# MEOWPOWER.net
KiCad netlist of a schematic drawn in Altium Designer
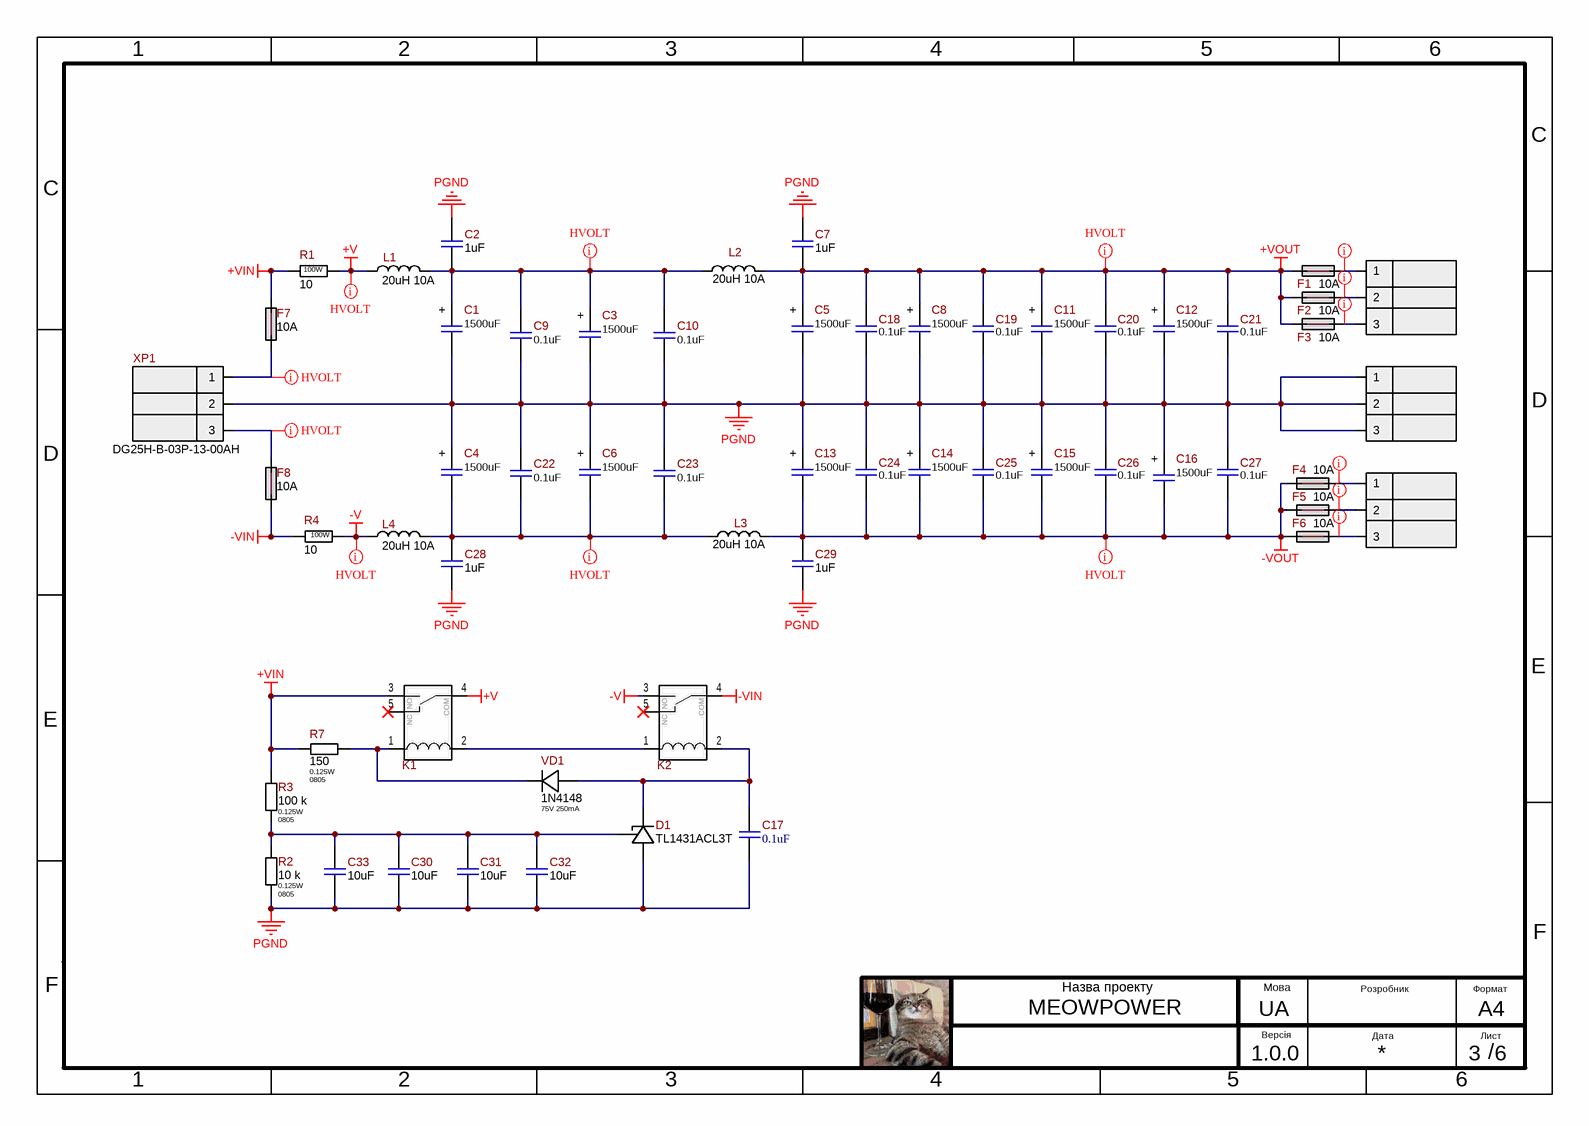
[diagram p0: MEOWPOWER.SchDoc]

(export (version "E")
  (design (tool "Eeschema 10.0.6"))
  (components
    (comp (ref "C1")
      (value "1500uF")
      (footprint "CAP-AE-PTH-180D05x400H20")
      (description "1500uF 50V")
      (fields (field (name "PART NUMBER") "1500uF  50V 18x35") (field (name "TOLERANCE") "±10%"))
      (libsource (lib "Database") (part "Capacitor_Electrolytic"))
    )
    (comp (ref "C2")
      (value "1uF")
      (footprint "CAP 25x10MM")
      (description "MKP 1uF 275V")
      (fields (field (name "PART NUMBER") "1uF  275V 25x10") (field (name "TOLERANCE") "±10%"))
      (libsource (lib "Database") (part "Capacitor_Ceramic"))
    )
    (comp (ref "C3")
      (value "1500uF")
      (footprint "CAP-AE-PTH-180D05x400H20")
      (description "1500uF 50V")
      (fields (field (name "PART NUMBER") "1500uF  50V 18x35") (field (name "TOLERANCE") "±10%"))
      (libsource (lib "Database") (part "Capacitor_Electrolytic"))
    )
    (comp (ref "C4")
      (value "1500uF")
      (footprint "CAP-AE-PTH-180D05x400H20")
      (description "1500uF 50V")
      (fields (field (name "PART NUMBER") "1500uF  50V 18x35") (field (name "TOLERANCE") "±10%"))
      (libsource (lib "Database") (part "Capacitor_Electrolytic"))
    )
    (comp (ref "C5")
      (value "1500uF")
      (footprint "CAP-AE-PTH-180D05x400H20")
      (description "1500uF 50V")
      (fields (field (name "PART NUMBER") "1500uF  50V 18x35") (field (name "TOLERANCE") "±10%"))
      (libsource (lib "Database") (part "Capacitor_Electrolytic"))
    )
    (comp (ref "C6")
      (value "1500uF")
      (footprint "CAP-AE-PTH-180D05x400H20")
      (description "1500uF 50V")
      (fields (field (name "PART NUMBER") "1500uF  50V 18x35") (field (name "TOLERANCE") "±10%"))
      (libsource (lib "Database") (part "Capacitor_Electrolytic"))
    )
    (comp (ref "C7")
      (value "1uF")
      (footprint "CAP 25x10MM")
      (description "MKP 1uF 275V")
      (fields (field (name "PART NUMBER") "1uF  275V 25x10") (field (name "TOLERANCE") "±10%"))
      (libsource (lib "Database") (part "Capacitor_Ceramic"))
    )
    (comp (ref "C8")
      (value "1500uF")
      (footprint "CAP-AE-PTH-180D05x400H20")
      (description "1500uF 50V")
      (fields (field (name "PART NUMBER") "1500uF  50V 18x35") (field (name "TOLERANCE") "±10%"))
      (libsource (lib "Database") (part "Capacitor_Electrolytic"))
    )
    (comp (ref "C9")
      (value "0.1uF")
      (footprint "C1206(3216)")
      (description "CAP CER 0.1UF 50V X7R 1206")
      (fields (field (name "PART NUMBER") "0.1uF  50V С1206") (field (name "MANUFACTURER") "AVX Corporation"))
      (libsource (lib "Database") (part "Capacitor_Ceramic"))
    )
    (comp (ref "C10")
      (value "0.1uF")
      (footprint "C1206(3216)")
      (description "CAP CER 0.1UF 50V X7R 1206")
      (fields (field (name "PART NUMBER") "0.1uF  50V С1206") (field (name "MANUFACTURER") "AVX Corporation"))
      (libsource (lib "Database") (part "Capacitor_Ceramic"))
    )
    (comp (ref "C11")
      (value "1500uF")
      (footprint "CAP-AE-PTH-180D05x400H20")
      (description "1500uF 50V")
      (fields (field (name "PART NUMBER") "1500uF  50V 18x35") (field (name "TOLERANCE") "±10%"))
      (libsource (lib "Database") (part "Capacitor_Electrolytic"))
    )
    (comp (ref "C12")
      (value "1500uF")
      (footprint "CAP-AE-PTH-180D05x400H20")
      (description "1500uF 50V")
      (fields (field (name "PART NUMBER") "1500uF  50V 18x35") (field (name "TOLERANCE") "±10%"))
      (libsource (lib "Database") (part "Capacitor_Electrolytic"))
    )
    (comp (ref "C13")
      (value "1500uF")
      (footprint "CAP-AE-PTH-180D05x400H20")
      (description "1500uF 50V")
      (fields (field (name "PART NUMBER") "1500uF  50V 18x35") (field (name "TOLERANCE") "±10%"))
      (libsource (lib "Database") (part "Capacitor_Electrolytic"))
    )
    (comp (ref "C14")
      (value "1500uF")
      (footprint "CAP-AE-PTH-180D05x400H20")
      (description "1500uF 50V")
      (fields (field (name "PART NUMBER") "1500uF  50V 18x35") (field (name "TOLERANCE") "±10%"))
      (libsource (lib "Database") (part "Capacitor_Electrolytic"))
    )
    (comp (ref "C15")
      (value "1500uF")
      (footprint "CAP-AE-PTH-180D05x400H20")
      (description "1500uF 50V")
      (fields (field (name "PART NUMBER") "1500uF  50V 18x35") (field (name "TOLERANCE") "±10%"))
      (libsource (lib "Database") (part "Capacitor_Electrolytic"))
    )
    (comp (ref "C16")
      (value "1500uF")
      (footprint "CAP-AE-PTH-180D05x400H20")
      (description "1500uF 50V")
      (fields (field (name "PART NUMBER") "1500uF  50V 18x35") (field (name "TOLERANCE") "±10%"))
      (libsource (lib "Database") (part "Capacitor_Electrolytic"))
    )
    (comp (ref "C17")
      (value "0.1uF")
      (footprint "C0805(2012)")
      (description "CAP CER 0.1UF 50V X7R 0805")
      (fields (field (name "PART NUMBER") "0.1uF  50V C0805") (field (name "MANUFACTURER") "AVX Corporation"))
      (libsource (lib "Database") (part "Capacitor_Ceramic"))
    )
    (comp (ref "C18")
      (value "0.1uF")
      (footprint "C1206(3216)")
      (description "CAP CER 0.1UF 50V X7R 1206")
      (fields (field (name "PART NUMBER") "0.1uF  50V С1206") (field (name "MANUFACTURER") "AVX Corporation"))
      (libsource (lib "Database") (part "Capacitor_Ceramic"))
    )
    (comp (ref "C19")
      (value "0.1uF")
      (footprint "C1206(3216)")
      (description "CAP CER 0.1UF 50V X7R 1206")
      (fields (field (name "PART NUMBER") "0.1uF  50V С1206") (field (name "MANUFACTURER") "AVX Corporation"))
      (libsource (lib "Database") (part "Capacitor_Ceramic"))
    )
    (comp (ref "C20")
      (value "0.1uF")
      (footprint "C1206(3216)")
      (description "CAP CER 0.1UF 50V X7R 1206")
      (fields (field (name "PART NUMBER") "0.1uF  50V С1206") (field (name "MANUFACTURER") "AVX Corporation"))
      (libsource (lib "Database") (part "Capacitor_Ceramic"))
    )
    (comp (ref "C21")
      (value "0.1uF")
      (footprint "C1206(3216)")
      (description "CAP CER 0.1UF 50V X7R 1206")
      (fields (field (name "PART NUMBER") "0.1uF  50V С1206") (field (name "MANUFACTURER") "AVX Corporation"))
      (libsource (lib "Database") (part "Capacitor_Ceramic"))
    )
    (comp (ref "C22")
      (value "0.1uF")
      (footprint "C1206(3216)")
      (description "CAP CER 0.1UF 50V X7R 1206")
      (fields (field (name "PART NUMBER") "0.1uF  50V С1206") (field (name "MANUFACTURER") "AVX Corporation"))
      (libsource (lib "Database") (part "Capacitor_Ceramic"))
    )
    (comp (ref "C23")
      (value "0.1uF")
      (footprint "C1206(3216)")
      (description "CAP CER 0.1UF 50V X7R 1206")
      (fields (field (name "PART NUMBER") "0.1uF  50V С1206") (field (name "MANUFACTURER") "AVX Corporation"))
      (libsource (lib "Database") (part "Capacitor_Ceramic"))
    )
    (comp (ref "C24")
      (value "0.1uF")
      (footprint "C1206(3216)")
      (description "CAP CER 0.1UF 50V X7R 1206")
      (fields (field (name "PART NUMBER") "0.1uF  50V С1206") (field (name "MANUFACTURER") "AVX Corporation"))
      (libsource (lib "Database") (part "Capacitor_Ceramic"))
    )
    (comp (ref "C25")
      (value "0.1uF")
      (footprint "C1206(3216)")
      (description "CAP CER 0.1UF 50V X7R 1206")
      (fields (field (name "PART NUMBER") "0.1uF  50V С1206") (field (name "MANUFACTURER") "AVX Corporation"))
      (libsource (lib "Database") (part "Capacitor_Ceramic"))
    )
    (comp (ref "C26")
      (value "0.1uF")
      (footprint "C1206(3216)")
      (description "CAP CER 0.1UF 50V X7R 1206")
      (fields (field (name "PART NUMBER") "0.1uF  50V С1206") (field (name "MANUFACTURER") "AVX Corporation"))
      (libsource (lib "Database") (part "Capacitor_Ceramic"))
    )
    (comp (ref "C27")
      (value "0.1uF")
      (footprint "C1206(3216)")
      (description "CAP CER 0.1UF 50V X7R 1206")
      (fields (field (name "PART NUMBER") "0.1uF  50V С1206") (field (name "MANUFACTURER") "AVX Corporation"))
      (libsource (lib "Database") (part "Capacitor_Ceramic"))
    )
    (comp (ref "C28")
      (value "1uF")
      (footprint "CAP 25x10MM")
      (description "MKP 1uF 275V")
      (fields (field (name "PART NUMBER") "1uF  275V 25x10") (field (name "TOLERANCE") "±10%"))
      (libsource (lib "Database") (part "Capacitor_Ceramic"))
    )
    (comp (ref "C29")
      (value "1uF")
      (footprint "CAP 25x10MM")
      (description "MKP 1uF 275V")
      (fields (field (name "PART NUMBER") "1uF  275V 25x10") (field (name "TOLERANCE") "±10%"))
      (libsource (lib "Database") (part "Capacitor_Ceramic"))
    )
    (comp (ref "C30")
      (value "10uF")
      (footprint "C0805(2012)")
      (description "CAP CER 10UF 16V X6S 0805")
      (fields (field (name "PART NUMBER") "10uF  16V C0805") (field (name "TOLERANCE") "±10%"))
      (libsource (lib "Database") (part "Capacitor_Ceramic"))
    )
    (comp (ref "C31")
      (value "10uF")
      (footprint "C0805(2012)")
      (description "CAP CER 10UF 16V X6S 0805")
      (fields (field (name "PART NUMBER") "10uF  16V C0805") (field (name "TOLERANCE") "±10%"))
      (libsource (lib "Database") (part "Capacitor_Ceramic"))
    )
    (comp (ref "C32")
      (value "10uF")
      (footprint "C0805(2012)")
      (description "CAP CER 10UF 16V X6S 0805")
      (fields (field (name "PART NUMBER") "10uF  16V C0805") (field (name "TOLERANCE") "±10%"))
      (libsource (lib "Database") (part "Capacitor_Ceramic"))
    )
    (comp (ref "C33")
      (value "10uF")
      (footprint "C0805(2012)")
      (description "CAP CER 10UF 16V X6S 0805")
      (fields (field (name "PART NUMBER") "10uF  16V C0805") (field (name "TOLERANCE") "±10%"))
      (libsource (lib "Database") (part "Capacitor_Ceramic"))
    )
    (comp (ref "D1")
      (value "TL1431ACL3T")
      (footprint "SOT-23")
      (description "IC VREF SHUNT ADJ  ±0.25% SOT23-3")
      (fields (field (name "PART NUMBER") "TL1431ACL3T") (field (name "MANUFACTURER") "STMicroelectronics"))
      (libsource (lib "Database") (part "TL431"))
    )
    (comp (ref "F1")
      (value "10A")
      (footprint "FUSE1808")
      (libsource (lib "Database") (part "Resettable_Fuses"))
    )
    (comp (ref "F2")
      (value "10A")
      (footprint "FUSE1808")
      (libsource (lib "Database") (part "Resettable_Fuses"))
    )
    (comp (ref "F3")
      (value "10A")
      (footprint "FUSE1808")
      (libsource (lib "Database") (part "Resettable_Fuses"))
    )
    (comp (ref "F4")
      (value "10A")
      (footprint "FUSE1808")
      (libsource (lib "Database") (part "Resettable_Fuses"))
    )
    (comp (ref "F5")
      (value "10A")
      (footprint "FUSE1808")
      (libsource (lib "Database") (part "Resettable_Fuses"))
    )
    (comp (ref "F6")
      (value "10A")
      (footprint "FUSE1808")
      (libsource (lib "Database") (part "Resettable_Fuses"))
    )
    (comp (ref "F7") (value "10A") (footprint "FUSE1808") (libsource (lib "") (part "Resettable_Fuses_1")))
    (comp (ref "F8") (value "10A") (footprint "FUSE1808") (libsource (lib "") (part "Resettable_Fuses_1")))
    (comp (ref "K1")
      (value "LEG-12")
      (footprint "Relay10A")
      (description "General Purpose Relay, 1 Form C (1PDT), 12VDC 400Ohm Coil, 120VAC/24VDC @ 10A, 240VAC Max")
      (libsource (lib "Database") (part "RELAY10A"))
    )
    (comp (ref "K2")
      (value "LEG-12")
      (footprint "Relay10A")
      (description "General Purpose Relay, 1 Form C (1PDT), 12VDC 400Ohm Coil, 120VAC/24VDC @ 10A, 240VAC Max")
      (libsource (lib "Database") (part "RELAY10A"))
    )
    (comp (ref "L1")
      (value "20uH 10A")
      (footprint "IND10x25x8.4")
      (description "CASTOM")
      (fields (field (name "TOLERANCE") "±10"))
      (libsource (lib "Database") (part "INDUCTORS"))
    )
    (comp (ref "L2")
      (value "20uH 10A")
      (footprint "IND10x25x8.4")
      (description "CASTOM")
      (fields (field (name "TOLERANCE") "±10"))
      (libsource (lib "Database") (part "INDUCTORS"))
    )
    (comp (ref "L3")
      (value "20uH 10A")
      (footprint "IND10x25x8.4")
      (description "CASTOM")
      (fields (field (name "TOLERANCE") "±10"))
      (libsource (lib "Database") (part "INDUCTORS"))
    )
    (comp (ref "L4")
      (value "20uH 10A")
      (footprint "IND10x25x8.4")
      (description "CASTOM")
      (fields (field (name "TOLERANCE") "±10"))
      (libsource (lib "Database") (part "INDUCTORS"))
    )
    (comp (ref "R1")
      (value "10")
      (footprint "RES_TO-247")
      (description "Resistror 10 OHM  ±5% TO-247 100W")
      (fields
        (field (name "POWER RATING") "100W")
        (field (name "PART NUMBER") "10  RES_TO-247")
        (field (name "TOLERANCE") "±5%")
      )
      (libsource (lib "Database") (part "RES_1W"))
    )
    (comp (ref "R2")
      (value "10 k")
      (footprint "R0805")
      (description "RES SMD 10 k OHM  ±1% 1/8W 0805")
      (fields
        (field (name "POWER RATING") "0.125W")
        (field (name "PACKAGE/CASE") "0805")
        (field (name "PART NUMBER") "10 k  R0805")
        (field (name "TOLERANCE") "±1%")
      )
      (libsource (lib "Database") (part "R0805"))
    )
    (comp (ref "R3")
      (value "100 k")
      (footprint "R0805")
      (description "RES SMD 100 k OHM  ±1% 1/8W 0805")
      (fields
        (field (name "POWER RATING") "0.125W")
        (field (name "PACKAGE/CASE") "0805")
        (field (name "PART NUMBER") "100 k  R0805")
        (field (name "TOLERANCE") "±1%")
      )
      (libsource (lib "Database") (part "R0805"))
    )
    (comp (ref "R4")
      (value "10")
      (footprint "RES_TO-247")
      (description "Resistror 10 OHM  ±5% TO-247 100W")
      (fields
        (field (name "POWER RATING") "100W")
        (field (name "PART NUMBER") "10  RES_TO-247")
        (field (name "TOLERANCE") "±5%")
      )
      (libsource (lib "Database") (part "RES_1W"))
    )
    (comp (ref "R7")
      (value "150")
      (footprint "R0805")
      (description "RES SMD 150 OHM  ±1% 1/8W 0805")
      (fields
        (field (name "POWER RATING") "0.125W")
        (field (name "PACKAGE/CASE") "0805")
        (field (name "PART NUMBER") "150  R0805")
        (field (name "TOLERANCE") "±1%")
      )
      (libsource (lib "Database") (part "R0805"))
    )
    (comp (ref "VD1")
      (value "1N4148")
      (footprint "SOD-80")
      (description "DIODE GEN PURP 75V 250MA SOD323")
      (fields (field (name "POWER RATING") "75V 250mA") (field (name "MANUFACTURER") "Diodes Incorporated"))
      (libsource (lib "Database") (part "DIODE"))
    )
    (comp (ref "XP1")
      (value "DG25H-B-03P-13-00AH")
      (footprint "DG25H-B-03P")
      (description "3PIN 7.62mm 300V 15 A  7-30 AWG")
      (libsource (lib "") (part "CON_3_1"))
    )
    (comp (ref "XP2")
      (value "DG25H-B-03P-13-00AH")
      (footprint "DG25H-B-03P")
      (description "3PIN 7.62mm 300V 15 A  7-30 AWG")
      (libsource (lib "Database") (part "CON_3"))
    )
    (comp (ref "XP3")
      (value "DG25H-B-03P-13-00AH")
      (footprint "DG25H-B-03P")
      (description "3PIN 7.62mm 300V 15 A  7-30 AWG")
      (libsource (lib "Database") (part "CON_3"))
    )
    (comp (ref "XP4")
      (value "DG25H-B-03P-13-00AH")
      (footprint "DG25H-B-03P")
      (description "3PIN 7.62mm 300V 15 A  7-30 AWG")
      (libsource (lib "Database") (part "CON_3"))
    )
  )
  (nets
    (net (code "1") (name "+V") (class "Default")
      (node (ref "K1") (pin "4") (pinfunction "COM_4") (pintype "passive"))
      (node (ref "L1") (pin "1") (pintype "passive"))
      (node (ref "R1") (pin "2") (pinfunction "2_2") (pintype "passive"))
    )
    (net (code "2") (name "+VIN") (class "Default")
      (node (ref "F7") (pin "2") (pinfunction "2_2") (pintype "passive"))
      (node (ref "K1") (pin "3") (pinfunction "NO_3") (pintype "passive"))
      (node (ref "R1") (pin "1") (pinfunction "1_1") (pintype "passive"))
      (node (ref "R3") (pin "2") (pinfunction "2_2") (pintype "passive"))
      (node (ref "R7") (pin "2") (pinfunction "2_2") (pintype "passive"))
    )
    (net (code "3") (name "+VOUT") (class "Default")
      (node (ref "C11") (pin "1") (pinfunction "1_1") (pintype "passive"))
      (node (ref "C12") (pin "1") (pinfunction "1_1") (pintype "passive"))
      (node (ref "C18") (pin "1") (pinfunction "1_1") (pintype "passive"))
      (node (ref "C19") (pin "1") (pinfunction "1_1") (pintype "passive"))
      (node (ref "C20") (pin "1") (pinfunction "1_1") (pintype "passive"))
      (node (ref "C21") (pin "1") (pinfunction "1_1") (pintype "passive"))
      (node (ref "C5") (pin "1") (pinfunction "1_1") (pintype "passive"))
      (node (ref "C7") (pin "2") (pinfunction "2_2") (pintype "passive"))
      (node (ref "C8") (pin "1") (pinfunction "1_1") (pintype "passive"))
      (node (ref "F1") (pin "1") (pinfunction "1_1") (pintype "passive"))
      (node (ref "F2") (pin "1") (pinfunction "1_1") (pintype "passive"))
      (node (ref "F3") (pin "1") (pinfunction "1_1") (pintype "passive"))
      (node (ref "L2") (pin "2") (pintype "passive"))
    )
    (net (code "4") (name "-V") (class "Default")
      (node (ref "K2") (pin "3") (pinfunction "NO_3") (pintype "passive"))
      (node (ref "L4") (pin "1") (pintype "passive"))
      (node (ref "R4") (pin "1") (pinfunction "1_1") (pintype "passive"))
    )
    (net (code "5") (name "-VIN") (class "Default")
      (node (ref "F8") (pin "1") (pinfunction "1_1") (pintype "passive"))
      (node (ref "K2") (pin "4") (pinfunction "COM_4") (pintype "passive"))
      (node (ref "R4") (pin "2") (pinfunction "2_2") (pintype "passive"))
    )
    (net (code "6") (name "-VOUT") (class "Default")
      (node (ref "C13") (pin "2") (pinfunction "2_2") (pintype "passive"))
      (node (ref "C14") (pin "2") (pinfunction "2_2") (pintype "passive"))
      (node (ref "C15") (pin "2") (pinfunction "2_2") (pintype "passive"))
      (node (ref "C16") (pin "2") (pinfunction "2_2") (pintype "passive"))
      (node (ref "C24") (pin "2") (pinfunction "2_2") (pintype "passive"))
      (node (ref "C25") (pin "2") (pinfunction "2_2") (pintype "passive"))
      (node (ref "C26") (pin "2") (pinfunction "2_2") (pintype "passive"))
      (node (ref "C27") (pin "2") (pinfunction "2_2") (pintype "passive"))
      (node (ref "C29") (pin "2") (pinfunction "2_2") (pintype "passive"))
      (node (ref "F4") (pin "1") (pinfunction "1_1") (pintype "passive"))
      (node (ref "F5") (pin "1") (pinfunction "1_1") (pintype "passive"))
      (node (ref "F6") (pin "1") (pinfunction "1_1") (pintype "passive"))
      (node (ref "L3") (pin "2") (pintype "passive"))
    )
    (net (code "7") (name "Net-(C1-Pad1)") (class "Default")
      (node (ref "C1") (pin "1") (pinfunction "1_1") (pintype "passive"))
      (node (ref "C10") (pin "2") (pinfunction "2_2") (pintype "passive"))
      (node (ref "C2") (pin "2") (pinfunction "2_2") (pintype "passive"))
      (node (ref "C3") (pin "1") (pinfunction "1_1") (pintype "passive"))
      (node (ref "C9") (pin "2") (pinfunction "2_2") (pintype "passive"))
      (node (ref "L1") (pin "2") (pintype "passive"))
      (node (ref "L2") (pin "1") (pintype "passive"))
    )
    (net (code "8") (name "Net-(C22-Pad1)") (class "Default")
      (node (ref "C22") (pin "1") (pinfunction "1_1") (pintype "passive"))
      (node (ref "C23") (pin "1") (pinfunction "1_1") (pintype "passive"))
      (node (ref "C28") (pin "2") (pinfunction "2_2") (pintype "passive"))
      (node (ref "C4") (pin "2") (pinfunction "2_2") (pintype "passive"))
      (node (ref "C6") (pin "2") (pinfunction "2_2") (pintype "passive"))
      (node (ref "L3") (pin "1") (pintype "passive"))
      (node (ref "L4") (pin "2") (pintype "passive"))
    )
    (net (code "9") (name "Net-(D1-C)") (class "Default")
      (node (ref "C17") (pin "2") (pinfunction "2_2") (pintype "passive"))
      (node (ref "D1") (pin "1") (pinfunction "C_1") (pintype "passive"))
      (node (ref "K2") (pin "2") (pintype "passive"))
      (node (ref "VD1") (pin "2") (pinfunction "A_2") (pintype "passive"))
    )
    (net (code "10") (name "Net-(D1-REF)") (class "Default")
      (node (ref "C30") (pin "2") (pinfunction "2_2") (pintype "passive"))
      (node (ref "C31") (pin "2") (pinfunction "2_2") (pintype "passive"))
      (node (ref "C32") (pin "2") (pinfunction "2_2") (pintype "passive"))
      (node (ref "C33") (pin "2") (pinfunction "2_2") (pintype "passive"))
      (node (ref "D1") (pin "2") (pinfunction "REF_2") (pintype "passive"))
      (node (ref "R2") (pin "2") (pinfunction "2_2") (pintype "passive"))
      (node (ref "R3") (pin "1") (pinfunction "1_1") (pintype "passive"))
    )
    (net (code "11") (name "Net-(F1-Pad2)") (class "Default")
      (node (ref "F1") (pin "2") (pinfunction "2_2") (pintype "passive"))
      (node (ref "XP2") (pin "1") (pinfunction "1_1") (pintype "passive"))
    )
    (net (code "12") (name "Net-(F2-Pad2)") (class "Default")
      (node (ref "F2") (pin "2") (pinfunction "2_2") (pintype "passive"))
      (node (ref "XP2") (pin "2") (pinfunction "2_2") (pintype "passive"))
    )
    (net (code "13") (name "Net-(F3-Pad2)") (class "Default")
      (node (ref "F3") (pin "2") (pinfunction "2_2") (pintype "passive"))
      (node (ref "XP2") (pin "3") (pinfunction "3_3") (pintype "passive"))
    )
    (net (code "14") (name "Net-(F4-Pad2)") (class "Default")
      (node (ref "F4") (pin "2") (pinfunction "2_2") (pintype "passive"))
      (node (ref "XP4") (pin "1") (pinfunction "1_1") (pintype "passive"))
    )
    (net (code "15") (name "Net-(F5-Pad2)") (class "Default")
      (node (ref "F5") (pin "2") (pinfunction "2_2") (pintype "passive"))
      (node (ref "XP4") (pin "2") (pinfunction "2_2") (pintype "passive"))
    )
    (net (code "16") (name "Net-(F6-Pad2)") (class "Default")
      (node (ref "F6") (pin "2") (pinfunction "2_2") (pintype "passive"))
      (node (ref "XP4") (pin "3") (pinfunction "3_3") (pintype "passive"))
    )
    (net (code "17") (name "Net-(F7-Pad1)") (class "Default")
      (node (ref "F7") (pin "1") (pinfunction "1_1") (pintype "passive"))
      (node (ref "XP1") (pin "1") (pinfunction "1_1") (pintype "passive"))
    )
    (net (code "18") (name "Net-(F8-Pad2)") (class "Default")
      (node (ref "F8") (pin "2") (pinfunction "2_2") (pintype "passive"))
      (node (ref "XP1") (pin "3") (pinfunction "3_3") (pintype "passive"))
    )
    (net (code "19") (name "Net-(K1-Pad2)") (class "Default")
      (node (ref "K1") (pin "2") (pintype "passive"))
      (node (ref "K2") (pin "1") (pintype "passive"))
    )
    (net (code "20") (name "Net-(VD1-K)") (class "Default")
      (node (ref "K1") (pin "1") (pintype "passive"))
      (node (ref "R7") (pin "1") (pinfunction "1_1") (pintype "passive"))
      (node (ref "VD1") (pin "1") (pinfunction "K_1") (pintype "passive"))
    )
    (net (code "21") (name "PGND") (class "Default")
      (node (ref "C1") (pin "2") (pinfunction "2_2") (pintype "passive"))
      (node (ref "C10") (pin "1") (pinfunction "1_1") (pintype "passive"))
      (node (ref "C11") (pin "2") (pinfunction "2_2") (pintype "passive"))
      (node (ref "C12") (pin "2") (pinfunction "2_2") (pintype "passive"))
      (node (ref "C13") (pin "1") (pinfunction "1_1") (pintype "passive"))
      (node (ref "C14") (pin "1") (pinfunction "1_1") (pintype "passive"))
      (node (ref "C15") (pin "1") (pinfunction "1_1") (pintype "passive"))
      (node (ref "C16") (pin "1") (pinfunction "1_1") (pintype "passive"))
      (node (ref "C17") (pin "1") (pinfunction "1_1") (pintype "passive"))
      (node (ref "C18") (pin "2") (pinfunction "2_2") (pintype "passive"))
      (node (ref "C19") (pin "2") (pinfunction "2_2") (pintype "passive"))
      (node (ref "C2") (pin "1") (pinfunction "1_1") (pintype "passive"))
      (node (ref "C20") (pin "2") (pinfunction "2_2") (pintype "passive"))
      (node (ref "C21") (pin "2") (pinfunction "2_2") (pintype "passive"))
      (node (ref "C22") (pin "2") (pinfunction "2_2") (pintype "passive"))
      (node (ref "C23") (pin "2") (pinfunction "2_2") (pintype "passive"))
      (node (ref "C24") (pin "1") (pinfunction "1_1") (pintype "passive"))
      (node (ref "C25") (pin "1") (pinfunction "1_1") (pintype "passive"))
      (node (ref "C26") (pin "1") (pinfunction "1_1") (pintype "passive"))
      (node (ref "C27") (pin "1") (pinfunction "1_1") (pintype "passive"))
      (node (ref "C28") (pin "1") (pinfunction "1_1") (pintype "passive"))
      (node (ref "C29") (pin "1") (pinfunction "1_1") (pintype "passive"))
      (node (ref "C3") (pin "2") (pinfunction "2_2") (pintype "passive"))
      (node (ref "C30") (pin "1") (pinfunction "1_1") (pintype "passive"))
      (node (ref "C31") (pin "1") (pinfunction "1_1") (pintype "passive"))
      (node (ref "C32") (pin "1") (pinfunction "1_1") (pintype "passive"))
      (node (ref "C33") (pin "1") (pinfunction "1_1") (pintype "passive"))
      (node (ref "C4") (pin "1") (pinfunction "1_1") (pintype "passive"))
      (node (ref "C5") (pin "2") (pinfunction "2_2") (pintype "passive"))
      (node (ref "C6") (pin "1") (pinfunction "1_1") (pintype "passive"))
      (node (ref "C7") (pin "1") (pinfunction "1_1") (pintype "passive"))
      (node (ref "C8") (pin "2") (pinfunction "2_2") (pintype "passive"))
      (node (ref "C9") (pin "1") (pinfunction "1_1") (pintype "passive"))
      (node (ref "D1") (pin "3") (pinfunction "A_3") (pintype "passive"))
      (node (ref "R2") (pin "1") (pinfunction "1_1") (pintype "passive"))
      (node (ref "XP1") (pin "2") (pinfunction "2_2") (pintype "passive"))
      (node (ref "XP3") (pin "1") (pinfunction "1_1") (pintype "passive"))
      (node (ref "XP3") (pin "2") (pinfunction "2_2") (pintype "passive"))
      (node (ref "XP3") (pin "3") (pinfunction "3_3") (pintype "passive"))
    )
    (net (code "22") (name "unconnected-(K1-NC-Pad5)") (class "Default")
      (node (ref "K1") (pin "5") (pinfunction "NC_5") (pintype "passive+no_connect"))
    )
    (net (code "23") (name "unconnected-(K2-NC-Pad5)") (class "Default")
      (node (ref "K2") (pin "5") (pinfunction "NC_5") (pintype "passive+no_connect"))
    )
  )
)
